# ADC_for_Arduino.net
KiCad netlist of a schematic drawn in EAGLE
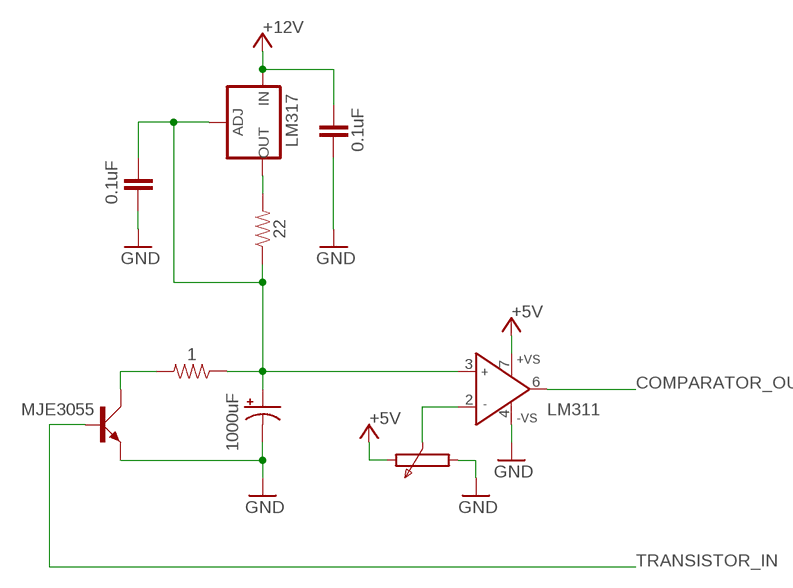
[diagram p0: schematic, sheet 1]

(export (version "E")
  (design (tool "Eeschema 10.0.6"))
  (components
    (comp (ref "C1")
      (value "1000uF")
      (footprint "eagle-import:CPOL-RADIAL-5MM-10MM")
      (libsource (lib "eagle-import") (part "1000UF-RADIAL-5MM-25V-20%"))
    )
    (comp (ref "C2")
      (value "0.1uF")
      (footprint "eagle-import:C025-025X050")
      (libsource (lib "eagle-import") (part "C-EU025-025X050"))
    )
    (comp (ref "C3")
      (value "C-EU025-025X050")
      (footprint "eagle-import:C025-025X050")
      (fields (field (name "SPICEPREFIX") "C") (field (name "SPICEPREFIX_1") "0.1uF"))
      (libsource (lib "eagle-import") (part "C-EU025-025X050"))
    )
    (comp (ref "IC1")
      (value "LM311")
      (footprint "eagle-import:SO8")
      (fields (field (name "MF") "ALTERA CORPORATION") (field (name "MPN") "AD825ARZ"))
      (libsource (lib "eagle-import") (part "AD825R"))
    )
    (comp (ref "Q1")
      (value "MJE3055")
      (footprint "eagle-import:TO220AV")
      (libsource (lib "eagle-import") (part "MJE3055"))
    )
    (comp (ref "R1")
      (value "22")
      (footprint "eagle-import:0603")
      (libsource (lib "eagle-import") (part "10MOHM-0603-1/10W-5%"))
    )
    (comp (ref "R2")
      (value "1")
      (footprint "eagle-import:0603")
      (libsource (lib "eagle-import") (part "10MOHM-0603-1/10W-5%"))
    )
    (comp (ref "U1")
      (value "LM317")
      (footprint "eagle-import:SOT223")
      (libsource (lib "eagle-import") (part "V_REG_317SMD"))
    )
  )
  (nets
    (net (code "1") (name "+12V") (class "Default")
      (node (ref "C3") (pin "1") (pinfunction "1_1") (pintype "passive"))
      (node (ref "U1") (pin "3") (pinfunction "IN_3") (pintype "input"))
    )
    (net (code "2") (name "/COMPARATOR_OUT") (class "Default")
      (node (ref "IC1") (pin "6") (pinfunction "OUT_6") (pintype "output"))
    )
    (net (code "3") (name "/TRANSISTOR_IN") (class "Default")
      (node (ref "Q1") (pin "B") (pinfunction "B_B") (pintype "passive"))
    )
    (net (code "4") (name "GND") (class "Default")
      (node (ref "C1") (pin "-") (pinfunction "-_-") (pintype "passive"))
      (node (ref "C2") (pin "2") (pinfunction "2_2") (pintype "passive"))
      (node (ref "C3") (pin "2") (pinfunction "2_2") (pintype "passive"))
      (node (ref "IC1") (pin "4") (pinfunction "-VS_4") (pintype "input"))
      (node (ref "Q1") (pin "E") (pinfunction "E_E") (pintype "passive"))
    )
    (net (code "5") (name "Net-(IC1-IN+)") (class "Default")
      (node (ref "C1") (pin "+") (pinfunction "+_+") (pintype "passive"))
      (node (ref "C2") (pin "1") (pinfunction "1_1") (pintype "passive"))
      (node (ref "IC1") (pin "3") (pinfunction "IN+_3") (pintype "input"))
      (node (ref "R1") (pin "1") (pinfunction "1_1") (pintype "passive"))
      (node (ref "R2") (pin "1") (pinfunction "1_1") (pintype "passive"))
      (node (ref "U1") (pin "1") (pinfunction "ADJ_1") (pintype "input"))
    )
    (net (code "6") (name "Net-(Q1-PadC)") (class "Default")
      (node (ref "Q1") (pin "C") (pinfunction "C_C") (pintype "passive"))
      (node (ref "R2") (pin "2") (pinfunction "2_2") (pintype "passive"))
    )
    (net (code "7") (name "Net-(U1-OUT)") (class "Default")
      (node (ref "R1") (pin "2") (pinfunction "2_2") (pintype "passive"))
      (node (ref "U1") (pin "2") (pinfunction "OUT_2") (pintype "output"))
    )
    (net (code "8") (name "VCC") (class "Default")
      (node (ref "IC1") (pin "7") (pinfunction "+VS_7") (pintype "input"))
    )
    (net (code "9") (name "unconnected-(IC1-IN--Pad2)") (class "Default")
      (node (ref "IC1") (pin "2") (pinfunction "IN-_2") (pintype "input"))
    )
  )
)
